# ProPrj___2025-12-14-16-11-23.net
KiCad netlist of a schematic drawn in EasyEDA Pro
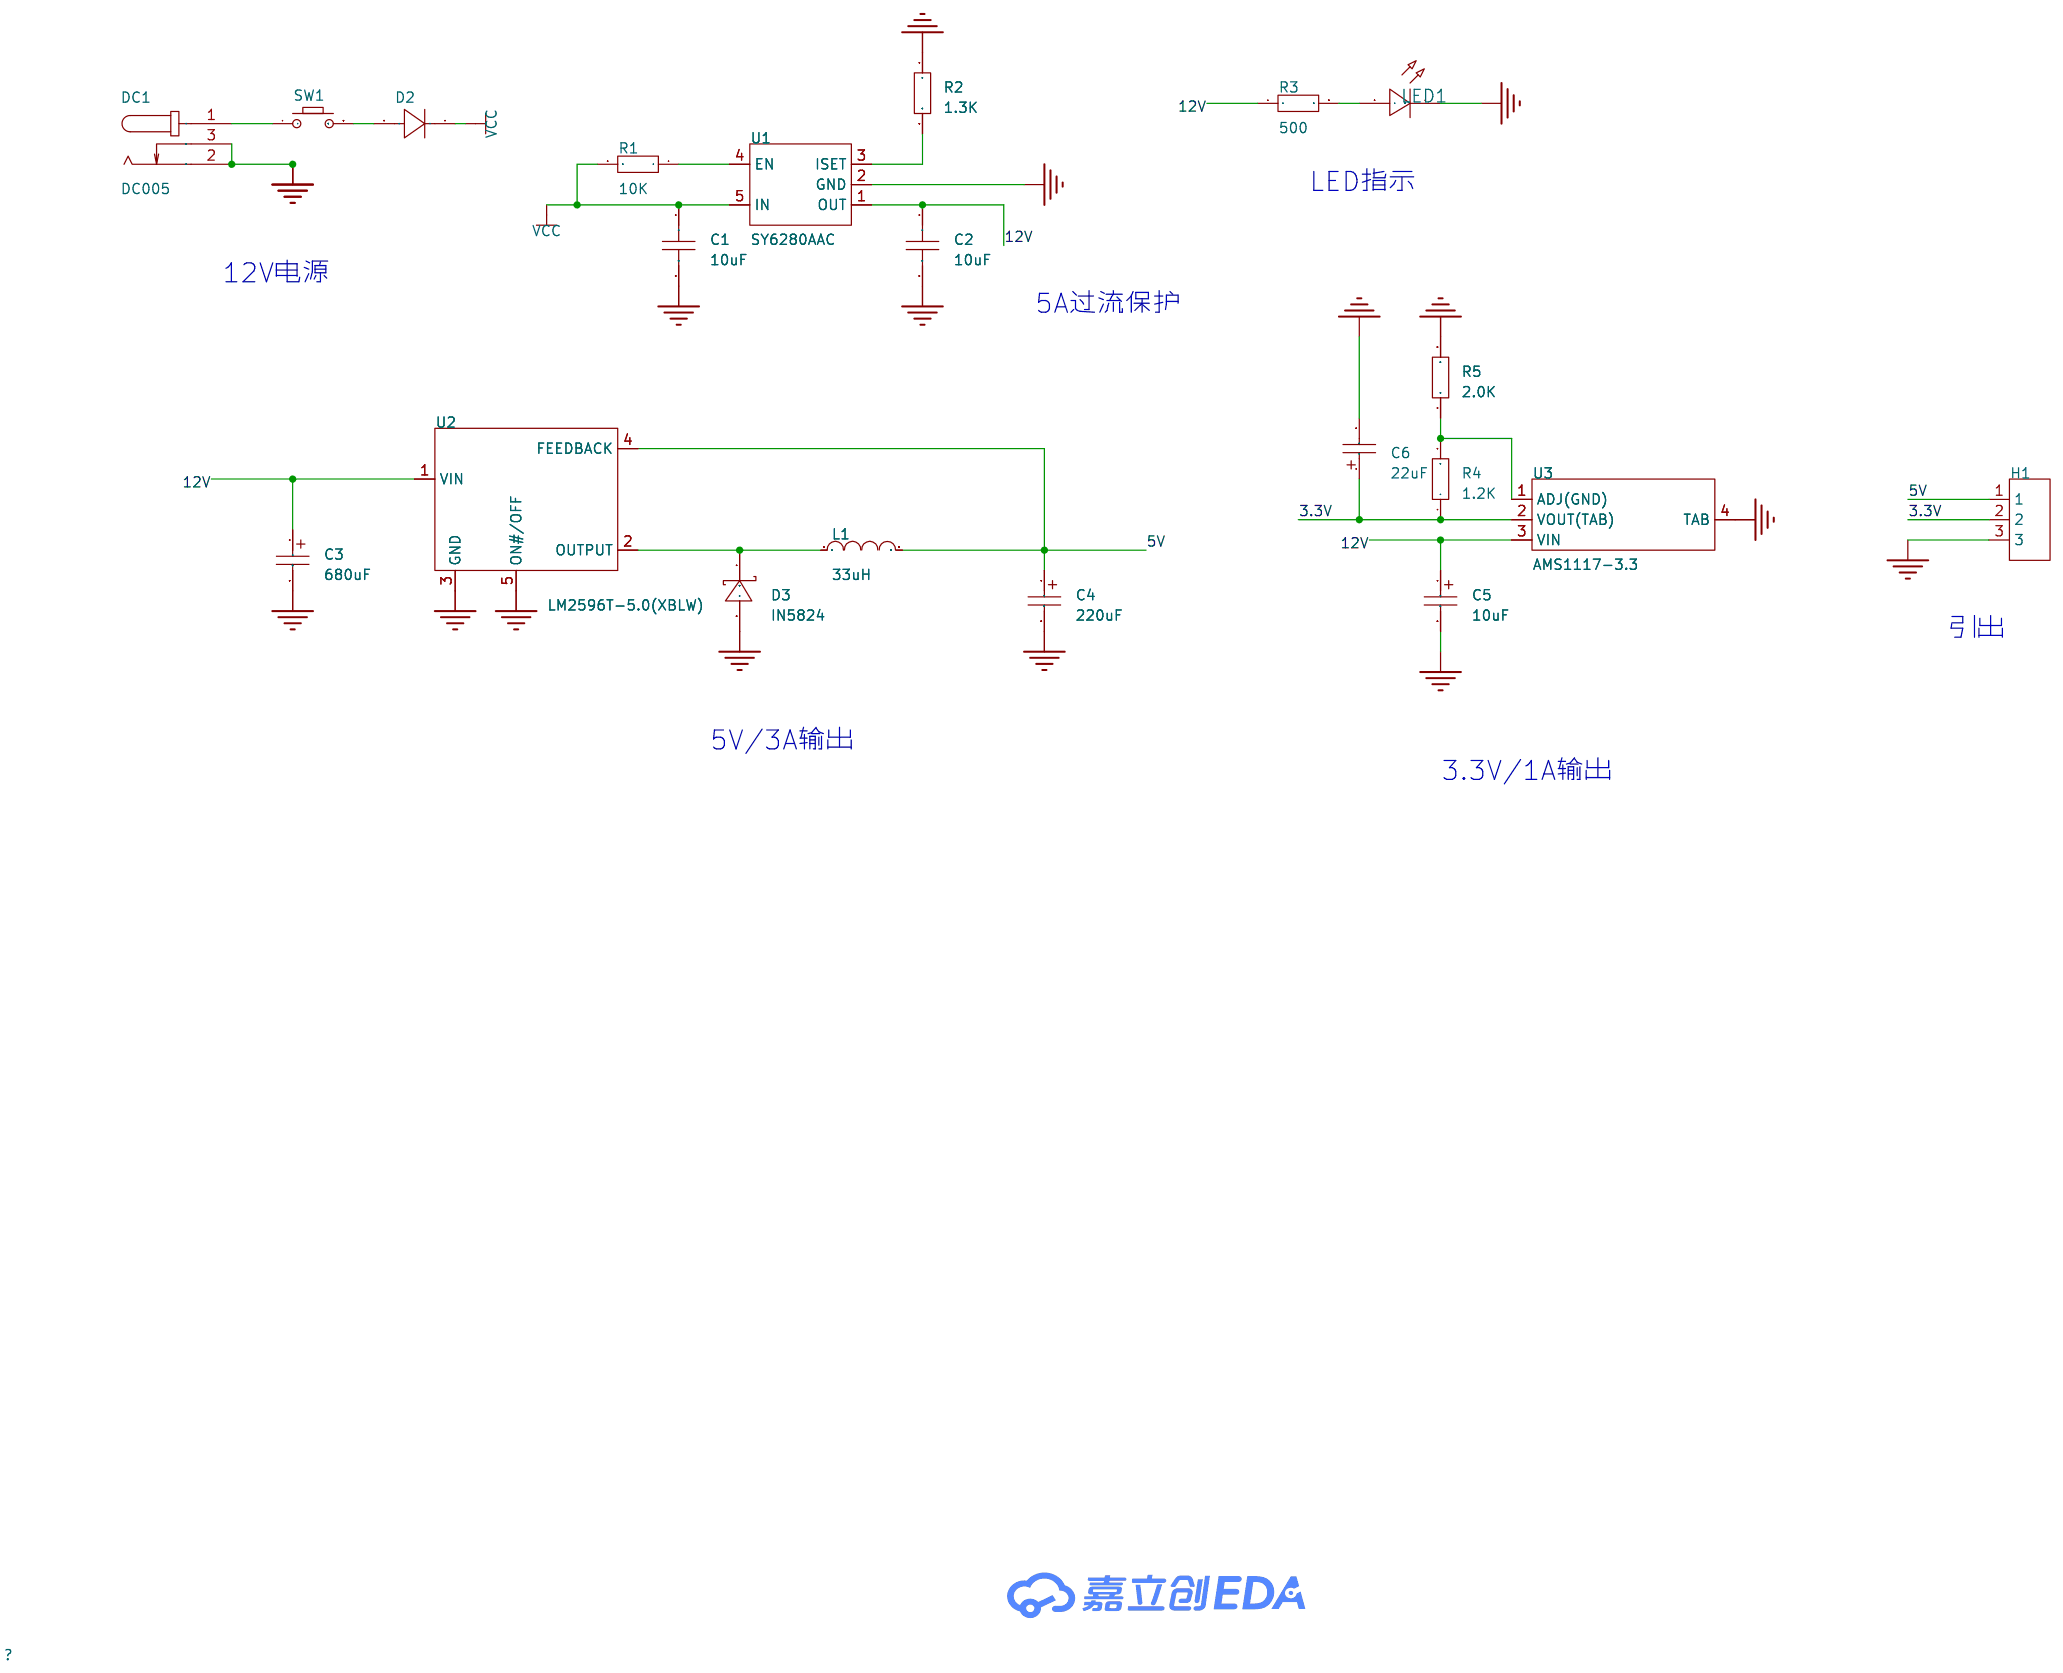
[diagram p0: schematic sheet]

(export (version "E")
  (design (tool "Eeschema 10.0.6"))
  (components
    (comp (ref "C1")
      (value "10uF")
      (footprint "easyedapro:C0603")
      (libsource (lib "easyedapro") (part "Capacitance"))
    )
    (comp (ref "C2")
      (value "10uF")
      (footprint "easyedapro:C0603")
      (libsource (lib "easyedapro") (part "Capacitance"))
    )
    (comp (ref "C3")
      (value "680uF")
      (footprint "easyedapro:C_Ele_SMD_3x5.4mm")
      (libsource (lib "easyedapro") (part "CAP"))
    )
    (comp (ref "C4")
      (value "220uF")
      (footprint "easyedapro:C_Ele_SMD_3x5.4mm")
      (libsource (lib "easyedapro") (part "CAP"))
    )
    (comp (ref "C5")
      (value "10uF")
      (footprint "easyedapro:C_Ele_SMD_3x5.4mm")
      (libsource (lib "easyedapro") (part "CAP"))
    )
    (comp (ref "C6")
      (value "22uF")
      (footprint "easyedapro:C_Ele_SMD_3x5.4mm")
      (libsource (lib "easyedapro") (part "CAP"))
    )
    (comp (ref "D2")
      (value "~")
      (footprint "easyedapro:DO_1N4007")
      (libsource (lib "easyedapro") (part "D_1N4007"))
    )
    (comp (ref "D3")
      (value "IN5824")
      (footprint "easyedapro:SMAF_L3.5-W2.6-LS4.7-RD")
      (libsource (lib "easyedapro") (part "IN5824"))
    )
    (comp (ref "DC1")
      (value "DC005")
      (footprint "easyedapro:DC-IN-TH_DC005")
      (description "连接器类型:DC电源插座;安装方式:弯插;触点内径:2mm;触点外径:6.3mm;额定电流:500mA;额定电压:12V;工作温度:-30°C~+70°C;")
      (fields (field (name "Manufacturer") "SHOU HAN(首韩)"))
      (libsource (lib "easyedapro") (part "DC005_C431533"))
    )
    (comp (ref "H1")
      (value "~")
      (footprint "easyedapro:HDR-TH_3P-P2.54-V-F")
      (libsource (lib "easyedapro") (part "PM254V-11-03-H85"))
    )
    (comp (ref "L1")
      (value "33uH")
      (footprint "easyedapro:L0603")
      (libsource (lib "easyedapro") (part "SDFL1608S100KTF"))
    )
    (comp (ref "LED1")
      (value "~")
      (footprint "easyedapro:LED_0603")
      (libsource (lib "easyedapro") (part "LED_R"))
    )
    (comp (ref "R1") (value "10K") (footprint "easyedapro:R0603") (libsource (lib "easyedapro") (part "电阻")))
    (comp (ref "R2") (value "1.3K") (footprint "easyedapro:R0603") (libsource (lib "easyedapro") (part "电阻")))
    (comp (ref "R3") (value "500") (footprint "easyedapro:R0603") (libsource (lib "easyedapro") (part "电阻")))
    (comp (ref "R4") (value "1.2K") (footprint "easyedapro:R0603") (libsource (lib "easyedapro") (part "电阻")))
    (comp (ref "R5") (value "2.0K") (footprint "easyedapro:R0603") (libsource (lib "easyedapro") (part "电阻")))
    (comp (ref "SW1")
      (value "~")
      (footprint "easyedapro:Key_TH_3.5x6x4.3")
      (libsource (lib "easyedapro") (part "Key_TH_3.5x6x4.3"))
    )
    (comp (ref "U1")
      (value "SY6280AAC")
      (footprint "easyedapro:SOT-23-5_L3.0-W1.7-P0.95-LS2.8-BR")
      (libsource (lib "easyedapro") (part "SY6280AAC_C9900003867"))
    )
    (comp (ref "U2")
      (value "LM2596T-5.0(XBLW)")
      (footprint "easyedapro:TO-220-5L_L10.2-W4.5-P1.71-L")
      (description "功能类型:降压型;工作电压:6V~40V;输出电压:5V;输出电流:3A;输出类型:固定;")
      (fields (field (name "Manufacturer") "XBLW(芯伯乐)"))
      (libsource (lib "easyedapro") (part "LM2596T-5.0(XBLW)"))
    )
    (comp (ref "U3")
      (value "AMS1117-3.3")
      (footprint "easyedapro:SOT-223-4_L6.5-W3.5-P2.30-LS7.0-BR")
      (description "输出类型:固定;工作电压:12V;输出电压:3.3V;输出电流:1A;电源纹波抑制比(PSRR):60dB@(120Hz);输出极性:正极;")
      (fields (field (name "Manufacturer") "UMW(友台半导体)"))
      (libsource (lib "easyedapro") (part "AMS1117-3.3_C347222"))
    )
  )
  (nets
    (net (code "1") (name "/3.3V") (class "Default")
      (node (ref "C6") (pin "1") (pinfunction "1_1") (pintype "input"))
      (node (ref "H1") (pin "2") (pinfunction "2_2") (pintype "unspecified"))
      (node (ref "R4") (pin "1") (pinfunction "1_1") (pintype "input"))
      (node (ref "U3") (pin "2") (pinfunction "VOUT(TAB)_2") (pintype "unspecified"))
    )
    (net (code "2") (name "/5V") (class "Default")
      (node (ref "C4") (pin "1") (pinfunction "1_1") (pintype "input"))
      (node (ref "H1") (pin "1") (pinfunction "1_1") (pintype "unspecified"))
      (node (ref "L1") (pin "2") (pinfunction "2_2") (pintype "unspecified"))
      (node (ref "U2") (pin "4") (pinfunction "FEEDBACK_4") (pintype "unspecified"))
    )
    (net (code "3") (name "/12V") (class "Default")
      (node (ref "C2") (pin "1") (pinfunction "1_1") (pintype "input"))
      (node (ref "C3") (pin "1") (pinfunction "1_1") (pintype "input"))
      (node (ref "C5") (pin "1") (pinfunction "1_1") (pintype "input"))
      (node (ref "R3") (pin "1") (pinfunction "1_1") (pintype "input"))
      (node (ref "U1") (pin "1") (pinfunction "OUT_1") (pintype "unspecified"))
      (node (ref "U2") (pin "1") (pinfunction "VIN_1") (pintype "unspecified"))
      (node (ref "U3") (pin "3") (pinfunction "VIN_3") (pintype "unspecified"))
    )
    (net (code "4") (name "GND") (class "Default")
      (node (ref "C1") (pin "2") (pinfunction "2_2") (pintype "input"))
      (node (ref "C2") (pin "2") (pinfunction "2_2") (pintype "input"))
      (node (ref "C3") (pin "2") (pinfunction "2_2") (pintype "input"))
      (node (ref "C4") (pin "2") (pinfunction "2_2") (pintype "input"))
      (node (ref "C5") (pin "2") (pinfunction "2_2") (pintype "input"))
      (node (ref "C6") (pin "2") (pinfunction "2_2") (pintype "input"))
      (node (ref "D3") (pin "2") (pinfunction "A_2") (pintype "unspecified"))
      (node (ref "DC1") (pin "2") (pinfunction "2_2") (pintype "unspecified"))
      (node (ref "DC1") (pin "3") (pinfunction "3_3") (pintype "unspecified"))
      (node (ref "H1") (pin "3") (pinfunction "3_3") (pintype "unspecified"))
      (node (ref "LED1") (pin "1") (pinfunction "C_1") (pintype "input"))
      (node (ref "R2") (pin "1") (pinfunction "1_1") (pintype "input"))
      (node (ref "R5") (pin "2") (pinfunction "2_2") (pintype "input"))
      (node (ref "U1") (pin "2") (pinfunction "GND_2") (pintype "unspecified"))
      (node (ref "U2") (pin "3") (pinfunction "GND_3") (pintype "unspecified"))
      (node (ref "U2") (pin "5") (pinfunction "ON#/OFF_5") (pintype "unspecified"))
      (node (ref "U3") (pin "4") (pinfunction "TAB_4") (pintype "unspecified"))
    )
    (net (code "5") (name "Net-(D2-A)") (class "Default")
      (node (ref "D2") (pin "2") (pinfunction "A_2") (pintype "input"))
      (node (ref "SW1") (pin "B") (pinfunction "B_B") (pintype "input"))
    )
    (net (code "6") (name "Net-(D3-C)") (class "Default")
      (node (ref "D3") (pin "1") (pinfunction "C_1") (pintype "unspecified"))
      (node (ref "L1") (pin "1") (pinfunction "1_1") (pintype "unspecified"))
      (node (ref "U2") (pin "2") (pinfunction "OUTPUT_2") (pintype "unspecified"))
    )
    (net (code "7") (name "Net-(DC1-Pad1)") (class "Default")
      (node (ref "DC1") (pin "1") (pinfunction "1_1") (pintype "unspecified"))
      (node (ref "SW1") (pin "A") (pinfunction "A_A") (pintype "input"))
    )
    (net (code "8") (name "Net-(LED1-A)") (class "Default")
      (node (ref "LED1") (pin "2") (pinfunction "A_2") (pintype "input"))
      (node (ref "R3") (pin "2") (pinfunction "2_2") (pintype "input"))
    )
    (net (code "9") (name "Net-(U1-EN)") (class "Default")
      (node (ref "R1") (pin "1") (pinfunction "1_1") (pintype "input"))
      (node (ref "U1") (pin "4") (pinfunction "EN_4") (pintype "unspecified"))
    )
    (net (code "10") (name "Net-(U1-ISET)") (class "Default")
      (node (ref "R2") (pin "2") (pinfunction "2_2") (pintype "input"))
      (node (ref "U1") (pin "3") (pinfunction "ISET_3") (pintype "unspecified"))
    )
    (net (code "11") (name "Net-(U3-ADJ(GND))") (class "Default")
      (node (ref "R4") (pin "2") (pinfunction "2_2") (pintype "input"))
      (node (ref "R5") (pin "1") (pinfunction "1_1") (pintype "input"))
      (node (ref "U3") (pin "1") (pinfunction "ADJ(GND)_1") (pintype "unspecified"))
    )
    (net (code "12") (name "VCC") (class "Default")
      (node (ref "C1") (pin "1") (pinfunction "1_1") (pintype "input"))
      (node (ref "D2") (pin "1") (pinfunction "K_1") (pintype "input"))
      (node (ref "R1") (pin "2") (pinfunction "2_2") (pintype "input"))
      (node (ref "U1") (pin "5") (pinfunction "IN_5") (pintype "unspecified"))
    )
  )
)
